# Power_board_2024.net
KiCad netlist of a schematic drawn in EAGLE
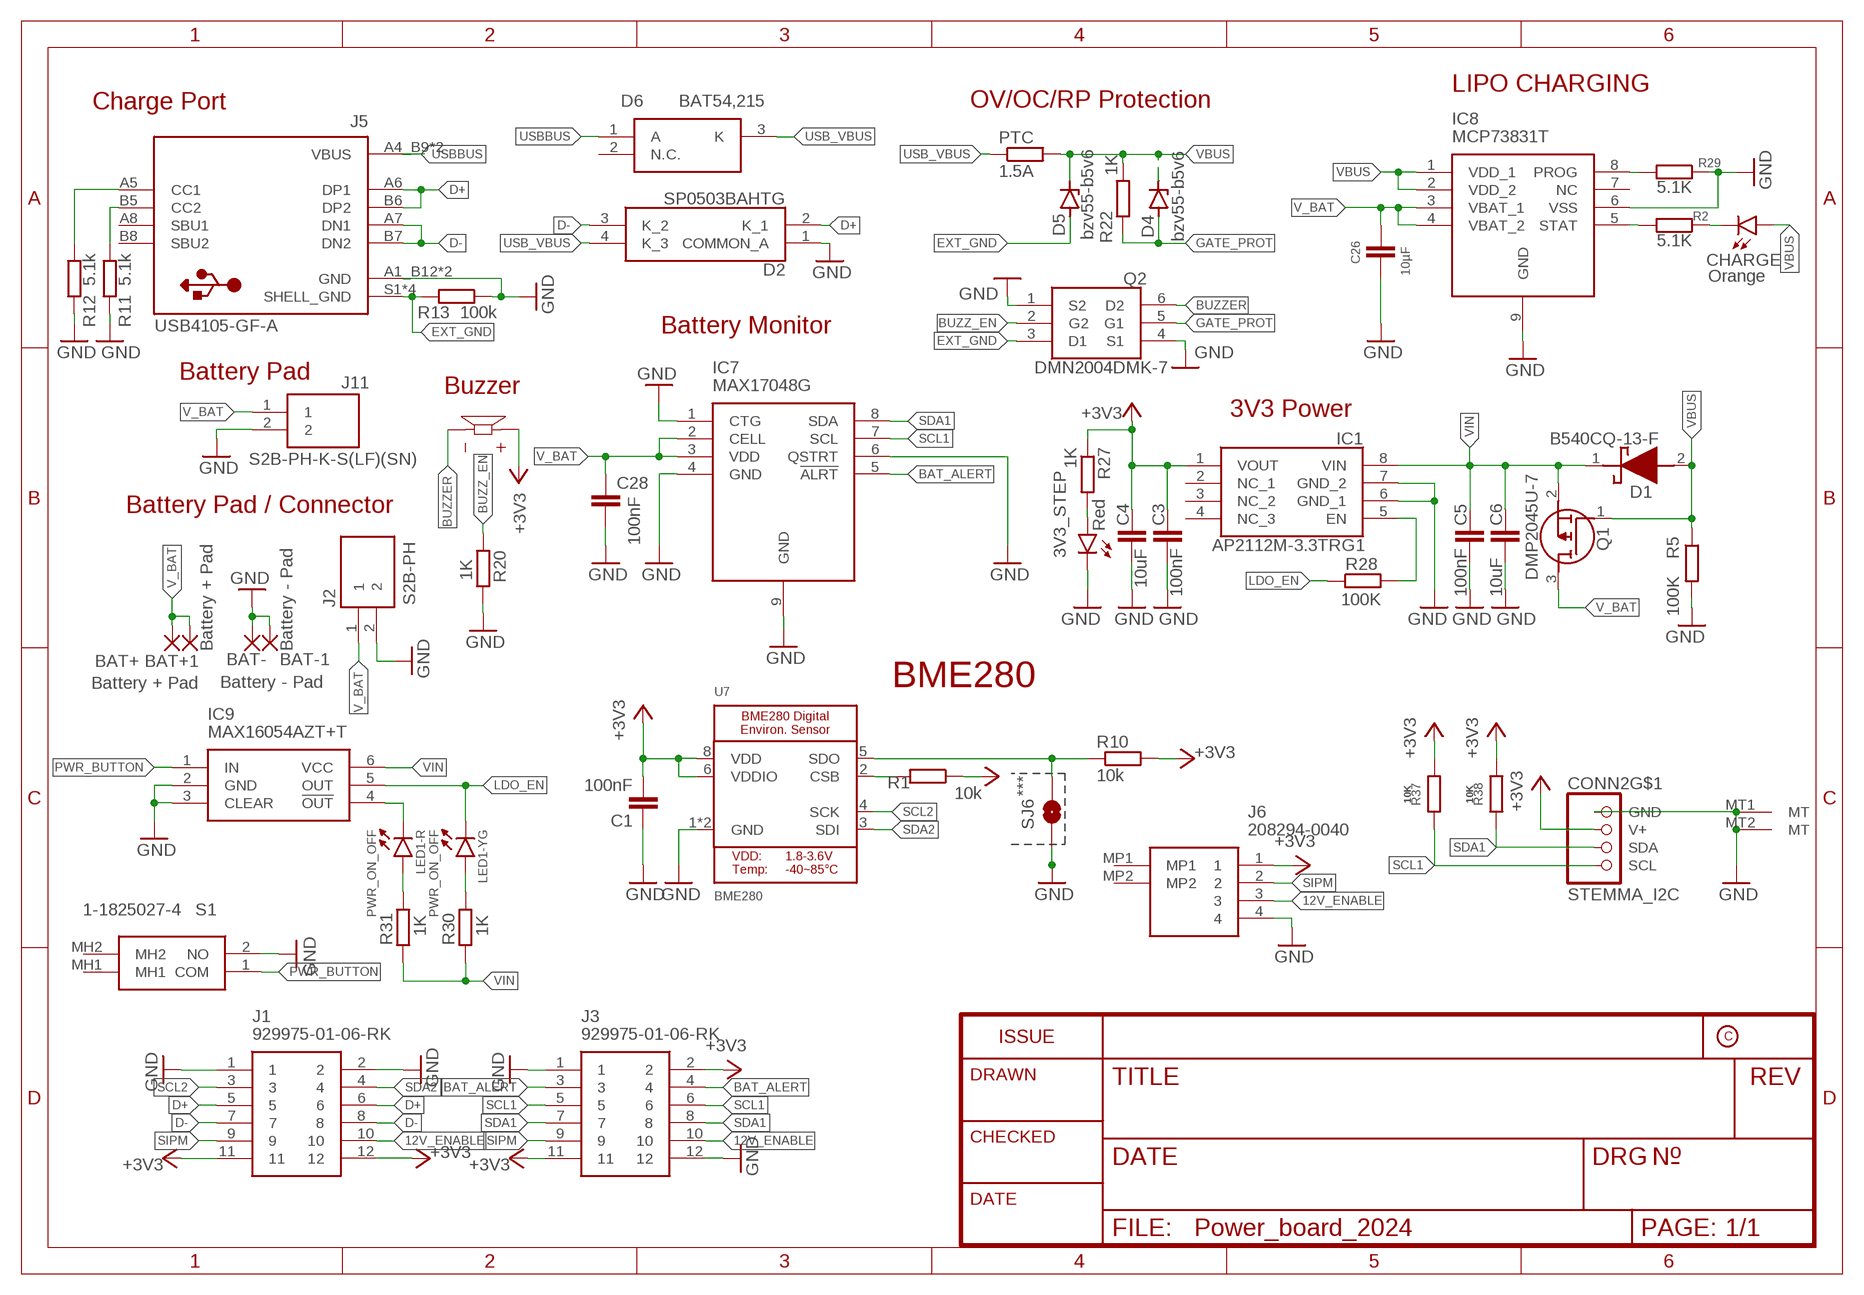
[diagram p0: schematic, sheet 1]

(export (version "E")
  (design (tool "Eeschema 10.0.6"))
  (components
    (comp (ref "3V3_STEP")
      (value "Red")
      (footprint "eagle-import:CHIPLED_0805")
      (libsource (lib "eagle-import") (part "LEDCHIPLED_0805"))
    )
    (comp (ref "BAT+")
      (value "Battery + Pad")
      (footprint "eagle-import:SMD2,54-5,08")
      (libsource (lib "eagle-import") (part "SMD5"))
    )
    (comp (ref "BAT+1")
      (value "Battery + Pad")
      (footprint "eagle-import:SMD2,54-5,08")
      (libsource (lib "eagle-import") (part "SMD5"))
    )
    (comp (ref "BAT-")
      (value "Battery - Pad")
      (footprint "eagle-import:SMD2,54-5,08")
      (libsource (lib "eagle-import") (part "SMD5"))
    )
    (comp (ref "BAT-1")
      (value "Battery - Pad")
      (footprint "eagle-import:SMD2,54-5,08")
      (libsource (lib "eagle-import") (part "SMD5"))
    )
    (comp (ref "BUZZER")
      (value "CMI-1210-5-95T")
      (footprint "eagle-import:XDCR_CMI-1210-5-95T")
      (fields (field (name "MANUFACTURER") "CUI Devices") (field (name "SPICEPREFIX") "B"))
      (libsource (lib "eagle-import") (part "CMI-1210-5-95T"))
    )
    (comp (ref "C1")
      (value "100nF")
      (footprint "eagle-import:C0603")
      (libsource (lib "eagle-import") (part "C-EUC0603"))
    )
    (comp (ref "C3")
      (value "100nF")
      (footprint "eagle-import:C0603")
      (libsource (lib "eagle-import") (part "C-EUC0603"))
    )
    (comp (ref "C4")
      (value "10uF")
      (footprint "eagle-import:C0603")
      (libsource (lib "eagle-import") (part "C-EUC0603"))
    )
    (comp (ref "C5")
      (value "100nF")
      (footprint "eagle-import:C0603")
      (libsource (lib "eagle-import") (part "C-EUC0603"))
    )
    (comp (ref "C6")
      (value "10uF")
      (footprint "eagle-import:C0603")
      (libsource (lib "eagle-import") (part "C-EUC0603"))
    )
    (comp (ref "C26")
      (value "10µF")
      (footprint "eagle-import:C0603")
      (libsource (lib "eagle-import") (part "C-EUC0603"))
    )
    (comp (ref "C28")
      (value "100nF")
      (footprint "eagle-import:C0603")
      (libsource (lib "eagle-import") (part "C-EUC0603"))
    )
    (comp (ref "CHARGE")
      (value "Orange")
      (footprint "eagle-import:CHIPLED_0805")
      (libsource (lib "eagle-import") (part "LEDCHIPLED_0805"))
    )
    (comp (ref "CONN2")
      (value "STEMMA_I2C")
      (footprint "eagle-import:JST_SH4")
      (libsource (lib "eagle-import") (part "STEMMA_I2C_QT"))
    )
    (comp (ref "D1")
      (value "B540CQ-13-F")
      (footprint "eagle-import:DIOM7959X250N")
      (fields (field (name "MOUSER_PART_NUMBER") "621-B540CQ-13-F"))
      (libsource (lib "eagle-import") (part "B540CQ-13-F"))
    )
    (comp (ref "D2")
      (value "SP0503BAHTG")
      (footprint "eagle-import:SP0503BAHTG")
      (fields (field (name "MOUSER_PART_NUMBER") "576-SP0503BAHTG"))
      (libsource (lib "eagle-import") (part "SP0503BAHTG"))
    )
    (comp (ref "D4")
      (value "bzv55-b5v6")
      (footprint "eagle-import:SOD80C")
      (libsource (lib "eagle-import") (part "ZENER-DIODESOD80C"))
    )
    (comp (ref "D5")
      (value "bzv55-b5v6")
      (footprint "eagle-import:SOD80C")
      (libsource (lib "eagle-import") (part "ZENER-DIODESOD80C"))
    )
    (comp (ref "D6")
      (value "BAT54,215")
      (footprint "eagle-import:SOT95P230X110-3N")
      (fields (field (name "MOUSER_PART_NUMBER") "771-BAT54-T/R"))
      (libsource (lib "eagle-import") (part "BAT54,215"))
    )
    (comp (ref "IC1")
      (value "AP2112M-3.3TRG1")
      (footprint "eagle-import:SOIC127P600X170-8N")
      (fields (field (name "MOUSER_PART_NUMBER") "621-AP2112M-3.3TRG1"))
      (libsource (lib "eagle-import") (part "AP2112M-3.3TRG1"))
    )
    (comp (ref "IC7")
      (value "MAX17048G")
      (footprint "eagle-import:SON50P200X200X80-9N")
      (fields
        (field (name "MANUFACTURER_PART_NUMBER") "MAX17048G+T10")
        (field (name "MOUSER_PART_NUMBER") "700-MAX17048G+T10")
      )
      (libsource (lib "eagle-import") (part "MAX17048G+T10"))
    )
    (comp (ref "IC8")
      (value "MCP73831T")
      (footprint "eagle-import:SON50P300X200X100-9N")
      (fields
        (field (name "MANUFACTURER_PART_NUMBER") "MCP73831T-2ACI/MC")
        (field (name "MOUSER_PART_NUMBER") "579-MCP73831T-2ACIMC")
      )
      (libsource (lib "eagle-import") (part "MCP73831T-2ACI_MC"))
    )
    (comp (ref "IC9")
      (value "MAX16054AZT+T")
      (footprint "eagle-import:SOT95P275X110-6N")
      (fields (field (name "MOUSER_PART_NUMBER") "700-MAX16054AZTT"))
      (libsource (lib "eagle-import") (part "MAX16054AZT+T"))
    )
    (comp (ref "J1")
      (value "929975-01-06-RK")
      (footprint "eagle-import:RHDR12W76P254_2X6_1524X508X839")
      (fields (field (name "MOUSER_PART_NUMBER") "517-929975-01-06-RK"))
      (libsource (lib "eagle-import") (part "929975-01-06-RK"))
    )
    (comp (ref "J2")
      (value "S2B-PH")
      (footprint "eagle-import:JST_S2B-PH-K-S(LF)(SN)")
      (fields (field (name "MF") "JST Sales America Inc.") (field (name "MP") "S2B-PH-K-S(LF)(SN)"))
      (libsource (lib "eagle-import") (part "S2B-PH-K-S(LF)(SN)"))
    )
    (comp (ref "J3")
      (value "929975-01-06-RK")
      (footprint "eagle-import:RHDR12W76P254_2X6_1524X508X839")
      (fields (field (name "MOUSER_PART_NUMBER") "517-929975-01-06-RK"))
      (libsource (lib "eagle-import") (part "929975-01-06-RK"))
    )
    (comp (ref "J5")
      (value "USB4105-GF-A")
      (footprint "eagle-import:GCT_USB4105-GF-A")
      (fields (field (name "MF") "GCT"))
      (libsource (lib "eagle-import") (part "USB4105-GF-A"))
    )
    (comp (ref "J6")
      (value "208294-0040")
      (footprint "eagle-import:2082940040")
      (fields (field (name "MOUSER_PART_NUMBER") "538-208294-0040"))
      (libsource (lib "eagle-import") (part "208294-0040"))
    )
    (comp (ref "J11")
      (value "S2B-PH-K-S(LF)(SN)")
      (footprint "eagle-import:JST_S2B-PH-K-S(LF)(SN)")
      (fields (field (name "MF") "JST Sales America Inc."))
      (libsource (lib "eagle-import") (part "S2B-PH-K-S(LF)(SN)"))
    )
    (comp (ref "LED1")
      (value "PWR_ON_OFF")
      (footprint "eagle-import:3216(1206)-4")
      (fields (field (name "MF") "OptoSupply") (field (name "MP") "OSRG1206C1C"))
      (libsource (lib "eagle-import") (part "OSRG1206C1C"))
    )
    (comp (ref "PTC")
      (value "1.5A")
      (footprint "eagle-import:R2512")
      (libsource (lib "eagle-import") (part "R-EU_R2512"))
    )
    (comp (ref "Q1")
      (value "DMP2045U-7")
      (footprint "eagle-import:SOT96P240X110-3N")
      (fields (field (name "MOUSER_PART_NUMBER") "621-DMP2045U-7"))
      (libsource (lib "eagle-import") (part "DMP2045U-7"))
    )
    (comp (ref "Q2")
      (value "DMN2004DMK-7")
      (footprint "eagle-import:SOT95P285X145-6N")
      (fields (field (name "MOUSER_PART_NUMBER") "621-DMN2004DMK-7"))
      (libsource (lib "eagle-import") (part "DMN2004DMK-7"))
    )
    (comp (ref "R1")
      (value "10k")
      (footprint "eagle-import:R0603")
      (libsource (lib "eagle-import") (part "R-EU_R0603"))
    )
    (comp (ref "R2")
      (value "5.1K")
      (footprint "eagle-import:R0603")
      (libsource (lib "eagle-import") (part "R-EU_R0603"))
    )
    (comp (ref "R5")
      (value "100K")
      (footprint "eagle-import:R0603")
      (libsource (lib "eagle-import") (part "R-EU_R0603"))
    )
    (comp (ref "R10")
      (value "10k")
      (footprint "eagle-import:R0603")
      (libsource (lib "eagle-import") (part "R-EU_R0603"))
    )
    (comp (ref "R11")
      (value "5.1k")
      (footprint "eagle-import:R0603")
      (libsource (lib "eagle-import") (part "R-EU_R0603"))
    )
    (comp (ref "R12")
      (value "5.1k")
      (footprint "eagle-import:R0603")
      (libsource (lib "eagle-import") (part "R-EU_R0603"))
    )
    (comp (ref "R13")
      (value "100k")
      (footprint "eagle-import:R0603")
      (libsource (lib "eagle-import") (part "R-EU_R0603"))
    )
    (comp (ref "R20")
      (value "1K")
      (footprint "eagle-import:R0603")
      (libsource (lib "eagle-import") (part "R-EU_R0603"))
    )
    (comp (ref "R22")
      (value "1K")
      (footprint "eagle-import:R0603")
      (libsource (lib "eagle-import") (part "R-EU_R0603"))
    )
    (comp (ref "R27")
      (value "1K")
      (footprint "eagle-import:R0603")
      (libsource (lib "eagle-import") (part "R-EU_R0603"))
    )
    (comp (ref "R28")
      (value "100K")
      (footprint "eagle-import:R0603")
      (libsource (lib "eagle-import") (part "R-EU_R0603"))
    )
    (comp (ref "R29")
      (value "5.1K")
      (footprint "eagle-import:R0603")
      (libsource (lib "eagle-import") (part "R-EU_R0603"))
    )
    (comp (ref "R30")
      (value "1K")
      (footprint "eagle-import:R0603")
      (libsource (lib "eagle-import") (part "R-EU_R0603"))
    )
    (comp (ref "R31")
      (value "1K")
      (footprint "eagle-import:R0603")
      (libsource (lib "eagle-import") (part "R-EU_R0603"))
    )
    (comp (ref "R37")
      (value "10K")
      (footprint "eagle-import:R0603")
      (libsource (lib "eagle-import") (part "R-EU_R0603"))
    )
    (comp (ref "R38")
      (value "10K")
      (footprint "eagle-import:R0603")
      (libsource (lib "eagle-import") (part "R-EU_R0603"))
    )
    (comp (ref "S1")
      (value "1-1825027-4")
      (footprint "eagle-import:118250274")
      (libsource (lib "eagle-import") (part "1-1825027-4"))
    )
    (comp (ref "SJ6")
      (value "SOLDER_JUMPER")
      (footprint "eagle-import:SPARKFUN_SJ_2S-NO")
      (libsource (lib "eagle-import") (part "SPARKFUN_SOLDERJUMPERNO"))
    )
    (comp (ref "U7")
      (value "BME280")
      (footprint "eagle-import:BME280")
      (libsource (lib "eagle-import") (part "BME280"))
    )
  )
  (nets
    (net (code "1") (name "+3V3") (class "Default")
      (node (ref "BUZZER") (pin "P") (pinfunction "P_P") (pintype "passive"))
      (node (ref "C1") (pin "2") (pinfunction "2_2") (pintype "passive"))
      (node (ref "C3") (pin "2") (pinfunction "2_2") (pintype "passive"))
      (node (ref "C4") (pin "2") (pinfunction "2_2") (pintype "passive"))
      (node (ref "CONN2") (pin "2") (pinfunction "V+_2") (pintype "passive"))
      (node (ref "IC1") (pin "1") (pinfunction "VOUT_1") (pintype "bidirectional"))
      (node (ref "J1") (pin "11") (pinfunction "11_11") (pintype "bidirectional"))
      (node (ref "J1") (pin "12") (pinfunction "12_12") (pintype "bidirectional"))
      (node (ref "J3") (pin "11") (pinfunction "11_11") (pintype "bidirectional"))
      (node (ref "J3") (pin "2") (pinfunction "2_2") (pintype "bidirectional"))
      (node (ref "J6") (pin "1") (pinfunction "1_1") (pintype "bidirectional"))
      (node (ref "R1") (pin "1") (pinfunction "1_1") (pintype "passive"))
      (node (ref "R10") (pin "2") (pinfunction "2_2") (pintype "passive"))
      (node (ref "R27") (pin "1") (pinfunction "1_1") (pintype "passive"))
      (node (ref "R37") (pin "2") (pinfunction "2_2") (pintype "passive"))
      (node (ref "R38") (pin "2") (pinfunction "2_2") (pintype "passive"))
      (node (ref "U7") (pin "6") (pinfunction "VDDIO_6") (pintype "power_in"))
      (node (ref "U7") (pin "8") (pinfunction "VDD_8") (pintype "power_in"))
    )
    (net (code "2") (name "12V_ENABLE") (class "Default")
      (node (ref "J1") (pin "10") (pinfunction "10_10") (pintype "bidirectional"))
      (node (ref "J3") (pin "10") (pinfunction "10_10") (pintype "bidirectional"))
      (node (ref "J6") (pin "3") (pinfunction "3_3") (pintype "bidirectional"))
    )
    (net (code "3") (name "BAT_ALERT") (class "Default")
      (node (ref "IC7") (pin "5") (pinfunction "~{ALRT}_5") (pintype "bidirectional"))
      (node (ref "J3") (pin "3") (pinfunction "3_3") (pintype "bidirectional"))
      (node (ref "J3") (pin "4") (pinfunction "4_4") (pintype "bidirectional"))
    )
    (net (code "4") (name "BUZZER") (class "Default")
      (node (ref "BUZZER") (pin "N") (pinfunction "N_N") (pintype "passive"))
      (node (ref "Q2") (pin "6") (pinfunction "D2_6") (pintype "bidirectional"))
    )
    (net (code "5") (name "BUZZ_EN") (class "Default")
      (node (ref "Q2") (pin "2") (pinfunction "G2_2") (pintype "bidirectional"))
      (node (ref "R20") (pin "1") (pinfunction "1_1") (pintype "passive"))
    )
    (net (code "6") (name "D+") (class "Default")
      (node (ref "D2") (pin "2") (pinfunction "K_1_2") (pintype "bidirectional"))
      (node (ref "J1") (pin "5") (pinfunction "5_5") (pintype "bidirectional"))
      (node (ref "J1") (pin "6") (pinfunction "6_6") (pintype "bidirectional"))
      (node (ref "J5") (pin "A6") (pinfunction "DP1_A6") (pintype "bidirectional"))
      (node (ref "J5") (pin "B6") (pinfunction "DP2_B6") (pintype "bidirectional"))
    )
    (net (code "7") (name "D-") (class "Default")
      (node (ref "D2") (pin "3") (pinfunction "K_2_3") (pintype "bidirectional"))
      (node (ref "J1") (pin "7") (pinfunction "7_7") (pintype "bidirectional"))
      (node (ref "J1") (pin "8") (pinfunction "8_8") (pintype "bidirectional"))
      (node (ref "J5") (pin "A7") (pinfunction "DN1_A7") (pintype "bidirectional"))
      (node (ref "J5") (pin "B7") (pinfunction "DN2_B7") (pintype "bidirectional"))
    )
    (net (code "8") (name "EXT_GND") (class "Default")
      (node (ref "D5") (pin "A") (pinfunction "A_A") (pintype "passive"))
      (node (ref "J5") (pin "S1") (pinfunction "SHELL_GND_S1") (pintype "power_in"))
      (node (ref "J5") (pin "S2") (pinfunction "SHELL_GND_S2") (pintype "power_in"))
      (node (ref "J5") (pin "S3") (pinfunction "SHELL_GND_S3") (pintype "power_in"))
      (node (ref "J5") (pin "S4") (pinfunction "SHELL_GND_S4") (pintype "power_in"))
      (node (ref "Q2") (pin "3") (pinfunction "D1_3") (pintype "bidirectional"))
      (node (ref "R13") (pin "2") (pinfunction "2_2") (pintype "passive"))
    )
    (net (code "9") (name "GATE_PROT") (class "Default")
      (node (ref "D4") (pin "A") (pinfunction "A_A") (pintype "passive"))
      (node (ref "Q2") (pin "5") (pinfunction "G1_5") (pintype "bidirectional"))
      (node (ref "R22") (pin "1") (pinfunction "1_1") (pintype "passive"))
    )
    (net (code "10") (name "GND") (class "Default")
      (node (ref "3V3_STEP") (pin "C") (pinfunction "C_C") (pintype "passive"))
      (node (ref "BAT-") (pin "1") (pinfunction "P_1") (pintype "passive"))
      (node (ref "BAT-1") (pin "1") (pinfunction "P_1") (pintype "passive"))
      (node (ref "C1") (pin "1") (pinfunction "1_1") (pintype "passive"))
      (node (ref "C26") (pin "2") (pinfunction "2_2") (pintype "passive"))
      (node (ref "C28") (pin "2") (pinfunction "2_2") (pintype "passive"))
      (node (ref "C3") (pin "1") (pinfunction "1_1") (pintype "passive"))
      (node (ref "C4") (pin "1") (pinfunction "1_1") (pintype "passive"))
      (node (ref "C5") (pin "1") (pinfunction "1_1") (pintype "passive"))
      (node (ref "C6") (pin "1") (pinfunction "1_1") (pintype "passive"))
      (node (ref "CONN2") (pin "1") (pinfunction "GND_1") (pintype "passive"))
      (node (ref "CONN2") (pin "MT1") (pinfunction "MT_MT1") (pintype "bidirectional"))
      (node (ref "CONN2") (pin "MT2") (pinfunction "MT_MT2") (pintype "bidirectional"))
      (node (ref "D2") (pin "1") (pinfunction "COMMON_A_1") (pintype "bidirectional"))
      (node (ref "IC1") (pin "6") (pinfunction "GND_1_6") (pintype "bidirectional"))
      (node (ref "IC1") (pin "7") (pinfunction "GND_2_7") (pintype "bidirectional"))
      (node (ref "IC7") (pin "1") (pinfunction "CTG_1") (pintype "bidirectional"))
      (node (ref "IC7") (pin "4") (pinfunction "GND_4") (pintype "bidirectional"))
      (node (ref "IC7") (pin "6") (pinfunction "QSTRT_6") (pintype "bidirectional"))
      (node (ref "IC7") (pin "9") (pinfunction "GND_9") (pintype "bidirectional"))
      (node (ref "IC8") (pin "6") (pinfunction "VSS_6") (pintype "bidirectional"))
      (node (ref "IC8") (pin "9") (pinfunction "GND_9") (pintype "bidirectional"))
      (node (ref "IC9") (pin "2") (pinfunction "GND_2") (pintype "bidirectional"))
      (node (ref "IC9") (pin "3") (pinfunction "CLEAR_3") (pintype "bidirectional"))
      (node (ref "J1") (pin "1") (pinfunction "1_1") (pintype "bidirectional"))
      (node (ref "J1") (pin "2") (pinfunction "2_2") (pintype "bidirectional"))
      (node (ref "J11") (pin "2") (pinfunction "2_2") (pintype "passive"))
      (node (ref "J2") (pin "2") (pinfunction "2_2") (pintype "passive"))
      (node (ref "J3") (pin "1") (pinfunction "1_1") (pintype "bidirectional"))
      (node (ref "J3") (pin "12") (pinfunction "12_12") (pintype "bidirectional"))
      (node (ref "J5") (pin "A1_B12") (pinfunction "GND_A1_B12") (pintype "power_in"))
      (node (ref "J5") (pin "B1_A12") (pinfunction "GND_B1_A12") (pintype "power_in"))
      (node (ref "J6") (pin "4") (pinfunction "4_4") (pintype "bidirectional"))
      (node (ref "Q2") (pin "1") (pinfunction "S2_1") (pintype "bidirectional"))
      (node (ref "Q2") (pin "4") (pinfunction "S1_4") (pintype "bidirectional"))
      (node (ref "R11") (pin "1") (pinfunction "1_1") (pintype "passive"))
      (node (ref "R12") (pin "1") (pinfunction "1_1") (pintype "passive"))
      (node (ref "R13") (pin "1") (pinfunction "1_1") (pintype "passive"))
      (node (ref "R20") (pin "2") (pinfunction "2_2") (pintype "passive"))
      (node (ref "R29") (pin "1") (pinfunction "1_1") (pintype "passive"))
      (node (ref "R5") (pin "2") (pinfunction "2_2") (pintype "passive"))
      (node (ref "S1") (pin "2") (pinfunction "NO_2") (pintype "bidirectional"))
      (node (ref "SJ6") (pin "1") (pinfunction "1_1") (pintype "passive"))
      (node (ref "U7") (pin "1") (pinfunction "GND_1") (pintype "power_in"))
      (node (ref "U7") (pin "7") (pinfunction "GND_7") (pintype "power_in"))
    )
    (net (code "11") (name "LDO_EN") (class "Default")
      (node (ref "IC9") (pin "5") (pinfunction "OUT_5") (pintype "bidirectional"))
      (node (ref "LED1") (pin "3") (pinfunction "C_3") (pintype "output"))
      (node (ref "R28") (pin "1") (pinfunction "1_1") (pintype "passive"))
    )
    (net (code "12") (name "Net-(3V3_STEP-PadA)") (class "Default")
      (node (ref "3V3_STEP") (pin "A") (pinfunction "A_A") (pintype "passive"))
      (node (ref "R27") (pin "2") (pinfunction "2_2") (pintype "passive"))
    )
    (net (code "13") (name "Net-(CHARGE-PadC)") (class "Default")
      (node (ref "CHARGE") (pin "C") (pinfunction "C_C") (pintype "passive"))
      (node (ref "R2") (pin "1") (pinfunction "1_1") (pintype "passive"))
    )
    (net (code "14") (name "Net-(IC1-EN)") (class "Default")
      (node (ref "IC1") (pin "5") (pinfunction "EN_5") (pintype "bidirectional"))
      (node (ref "R28") (pin "2") (pinfunction "2_2") (pintype "passive"))
    )
    (net (code "15") (name "Net-(IC8-PROG)") (class "Default")
      (node (ref "IC8") (pin "8") (pinfunction "PROG_8") (pintype "bidirectional"))
      (node (ref "R29") (pin "2") (pinfunction "2_2") (pintype "passive"))
    )
    (net (code "16") (name "Net-(IC8-STAT)") (class "Default")
      (node (ref "IC8") (pin "5") (pinfunction "STAT_5") (pintype "bidirectional"))
      (node (ref "R2") (pin "2") (pinfunction "2_2") (pintype "passive"))
    )
    (net (code "17") (name "Net-(IC9-~{OUT})") (class "Default")
      (node (ref "IC9") (pin "4") (pinfunction "~{OUT}_4") (pintype "bidirectional"))
      (node (ref "LED1") (pin "1") (pinfunction "C_1") (pintype "output"))
    )
    (net (code "18") (name "Net-(J5-CC1)") (class "Default")
      (node (ref "J5") (pin "A5") (pinfunction "CC1_A5") (pintype "bidirectional"))
      (node (ref "R12") (pin "2") (pinfunction "2_2") (pintype "passive"))
    )
    (net (code "19") (name "Net-(J5-CC2)") (class "Default")
      (node (ref "J5") (pin "B5") (pinfunction "CC2_B5") (pintype "bidirectional"))
      (node (ref "R11") (pin "2") (pinfunction "2_2") (pintype "passive"))
    )
    (net (code "20") (name "Net-(LED1A-A)") (class "Default")
      (node (ref "LED1") (pin "2") (pinfunction "A_2") (pintype "input"))
      (node (ref "R31") (pin "2") (pinfunction "2_2") (pintype "passive"))
    )
    (net (code "21") (name "Net-(LED1B-A)") (class "Default")
      (node (ref "LED1") (pin "4") (pinfunction "A_4") (pintype "input"))
      (node (ref "R30") (pin "2") (pinfunction "2_2") (pintype "passive"))
    )
    (net (code "22") (name "Net-(U7-CSB)") (class "Default")
      (node (ref "R1") (pin "2") (pinfunction "2_2") (pintype "passive"))
      (node (ref "U7") (pin "2") (pinfunction "CSB_2") (pintype "input"))
    )
    (net (code "23") (name "Net-(U7-SDO)") (class "Default")
      (node (ref "R10") (pin "1") (pinfunction "1_1") (pintype "passive"))
      (node (ref "SJ6") (pin "2") (pinfunction "2_2") (pintype "passive"))
      (node (ref "U7") (pin "5") (pinfunction "SDO_5") (pintype "output"))
    )
    (net (code "24") (name "PWR_BUTTON") (class "Default")
      (node (ref "IC9") (pin "1") (pinfunction "IN_1") (pintype "bidirectional"))
      (node (ref "S1") (pin "1") (pinfunction "COM_1") (pintype "bidirectional"))
    )
    (net (code "25") (name "SCL1") (class "Default")
      (node (ref "CONN2") (pin "4") (pinfunction "SCL_4") (pintype "passive"))
      (node (ref "IC7") (pin "7") (pinfunction "SCL_7") (pintype "bidirectional"))
      (node (ref "J3") (pin "5") (pinfunction "5_5") (pintype "bidirectional"))
      (node (ref "J3") (pin "6") (pinfunction "6_6") (pintype "bidirectional"))
      (node (ref "R37") (pin "1") (pinfunction "1_1") (pintype "passive"))
    )
    (net (code "26") (name "SCL2") (class "Default")
      (node (ref "J1") (pin "3") (pinfunction "3_3") (pintype "bidirectional"))
      (node (ref "U7") (pin "4") (pinfunction "SCK_4") (pintype "input"))
    )
    (net (code "27") (name "SDA1") (class "Default")
      (node (ref "CONN2") (pin "3") (pinfunction "SDA_3") (pintype "passive"))
      (node (ref "IC7") (pin "8") (pinfunction "SDA_8") (pintype "bidirectional"))
      (node (ref "J3") (pin "7") (pinfunction "7_7") (pintype "bidirectional"))
      (node (ref "J3") (pin "8") (pinfunction "8_8") (pintype "bidirectional"))
      (node (ref "R38") (pin "1") (pinfunction "1_1") (pintype "passive"))
    )
    (net (code "28") (name "SDA2") (class "Default")
      (node (ref "J1") (pin "4") (pinfunction "4_4") (pintype "bidirectional"))
      (node (ref "U7") (pin "3") (pinfunction "SDI_3") (pintype "input"))
    )
    (net (code "29") (name "SIPM") (class "Default")
      (node (ref "J1") (pin "9") (pinfunction "9_9") (pintype "bidirectional"))
      (node (ref "J3") (pin "9") (pinfunction "9_9") (pintype "bidirectional"))
      (node (ref "J6") (pin "2") (pinfunction "2_2") (pintype "bidirectional"))
    )
    (net (code "30") (name "USBBUS") (class "Default")
      (node (ref "D6") (pin "1") (pinfunction "A_1") (pintype "bidirectional"))
      (node (ref "J5") (pin "A4_B9") (pinfunction "VBUS_A4_B9") (pintype "power_in"))
      (node (ref "J5") (pin "B4_A9") (pinfunction "VBUS_B4_A9") (pintype "power_in"))
    )
    (net (code "31") (name "USB_VBUS") (class "Default")
      (node (ref "D2") (pin "4") (pinfunction "K_3_4") (pintype "bidirectional"))
      (node (ref "D6") (pin "3") (pinfunction "K_3") (pintype "bidirectional"))
      (node (ref "PTC") (pin "1") (pinfunction "1_1") (pintype "passive"))
    )
    (net (code "32") (name "VBUS") (class "Default")
      (node (ref "CHARGE") (pin "A") (pinfunction "A_A") (pintype "passive"))
      (node (ref "D1") (pin "2") (pinfunction "A_2") (pintype "bidirectional"))
      (node (ref "D4") (pin "C") (pinfunction "C_C") (pintype "passive"))
      (node (ref "D5") (pin "C") (pinfunction "C_C") (pintype "passive"))
      (node (ref "IC8") (pin "1") (pinfunction "VDD_1_1") (pintype "bidirectional"))
      (node (ref "IC8") (pin "2") (pinfunction "VDD_2_2") (pintype "bidirectional"))
      (node (ref "PTC") (pin "2") (pinfunction "2_2") (pintype "passive"))
      (node (ref "Q1") (pin "1") (pinfunction "G_1") (pintype "bidirectional"))
      (node (ref "R22") (pin "2") (pinfunction "2_2") (pintype "passive"))
      (node (ref "R5") (pin "1") (pinfunction "1_1") (pintype "passive"))
    )
    (net (code "33") (name "VIN") (class "Default")
      (node (ref "C5") (pin "2") (pinfunction "2_2") (pintype "passive"))
      (node (ref "C6") (pin "2") (pinfunction "2_2") (pintype "passive"))
      (node (ref "D1") (pin "1") (pinfunction "K_1") (pintype "bidirectional"))
      (node (ref "IC1") (pin "8") (pinfunction "VIN_8") (pintype "bidirectional"))
      (node (ref "IC9") (pin "6") (pinfunction "VCC_6") (pintype "bidirectional"))
      (node (ref "Q1") (pin "2") (pinfunction "S_2") (pintype "bidirectional"))
      (node (ref "R30") (pin "1") (pinfunction "1_1") (pintype "passive"))
      (node (ref "R31") (pin "1") (pinfunction "1_1") (pintype "passive"))
    )
    (net (code "34") (name "V_BAT") (class "Default")
      (node (ref "BAT+") (pin "1") (pinfunction "P_1") (pintype "passive"))
      (node (ref "BAT+1") (pin "1") (pinfunction "P_1") (pintype "passive"))
      (node (ref "C26") (pin "1") (pinfunction "1_1") (pintype "passive"))
      (node (ref "C28") (pin "1") (pinfunction "1_1") (pintype "passive"))
      (node (ref "IC7") (pin "2") (pinfunction "CELL_2") (pintype "bidirectional"))
      (node (ref "IC7") (pin "3") (pinfunction "VDD_3") (pintype "bidirectional"))
      (node (ref "IC8") (pin "3") (pinfunction "VBAT_1_3") (pintype "bidirectional"))
      (node (ref "IC8") (pin "4") (pinfunction "VBAT_2_4") (pintype "bidirectional"))
      (node (ref "J11") (pin "1") (pinfunction "1_1") (pintype "passive"))
      (node (ref "J2") (pin "1") (pinfunction "1_1") (pintype "passive"))
      (node (ref "Q1") (pin "3") (pinfunction "D_3") (pintype "bidirectional"))
    )
    (net (code "35") (name "unconnected-(D6-N.C.-Pad2)") (class "Default")
      (node (ref "D6") (pin "2") (pinfunction "N.C._2") (pintype "no_connect"))
    )
    (net (code "36") (name "unconnected-(IC1-NC_1-Pad2)") (class "Default")
      (node (ref "IC1") (pin "2") (pinfunction "NC_1_2") (pintype "bidirectional"))
    )
    (net (code "37") (name "unconnected-(IC1-NC_2-Pad3)") (class "Default")
      (node (ref "IC1") (pin "3") (pinfunction "NC_2_3") (pintype "bidirectional"))
    )
    (net (code "38") (name "unconnected-(IC1-NC_3-Pad4)") (class "Default")
      (node (ref "IC1") (pin "4") (pinfunction "NC_3_4") (pintype "bidirectional"))
    )
    (net (code "39") (name "unconnected-(IC8-NC-Pad7)") (class "Default")
      (node (ref "IC8") (pin "7") (pinfunction "NC_7") (pintype "no_connect"))
    )
    (net (code "40") (name "unconnected-(J5-SBU1-PadA8)") (class "Default")
      (node (ref "J5") (pin "A8") (pinfunction "SBU1_A8") (pintype "bidirectional"))
    )
    (net (code "41") (name "unconnected-(J5-SBU2-PadB8)") (class "Default")
      (node (ref "J5") (pin "B8") (pinfunction "SBU2_B8") (pintype "bidirectional"))
    )
    (net (code "42") (name "unconnected-(J6-PadMP1)") (class "Default")
      (node (ref "J6") (pin "MP1") (pinfunction "MP1_MP1") (pintype "bidirectional"))
    )
    (net (code "43") (name "unconnected-(J6-PadMP2)") (class "Default")
      (node (ref "J6") (pin "MP2") (pinfunction "MP2_MP2") (pintype "bidirectional"))
    )
    (net (code "44") (name "unconnected-(S1-PadMH1)") (class "Default")
      (node (ref "S1") (pin "MH1") (pinfunction "MH1_MH1") (pintype "bidirectional"))
    )
    (net (code "45") (name "unconnected-(S1-PadMH2)") (class "Default")
      (node (ref "S1") (pin "MH2") (pinfunction "MH2_MH2") (pintype "bidirectional"))
    )
  )
)
